# Power_supply.net
KiCad netlist of a schematic drawn in Altium Designer
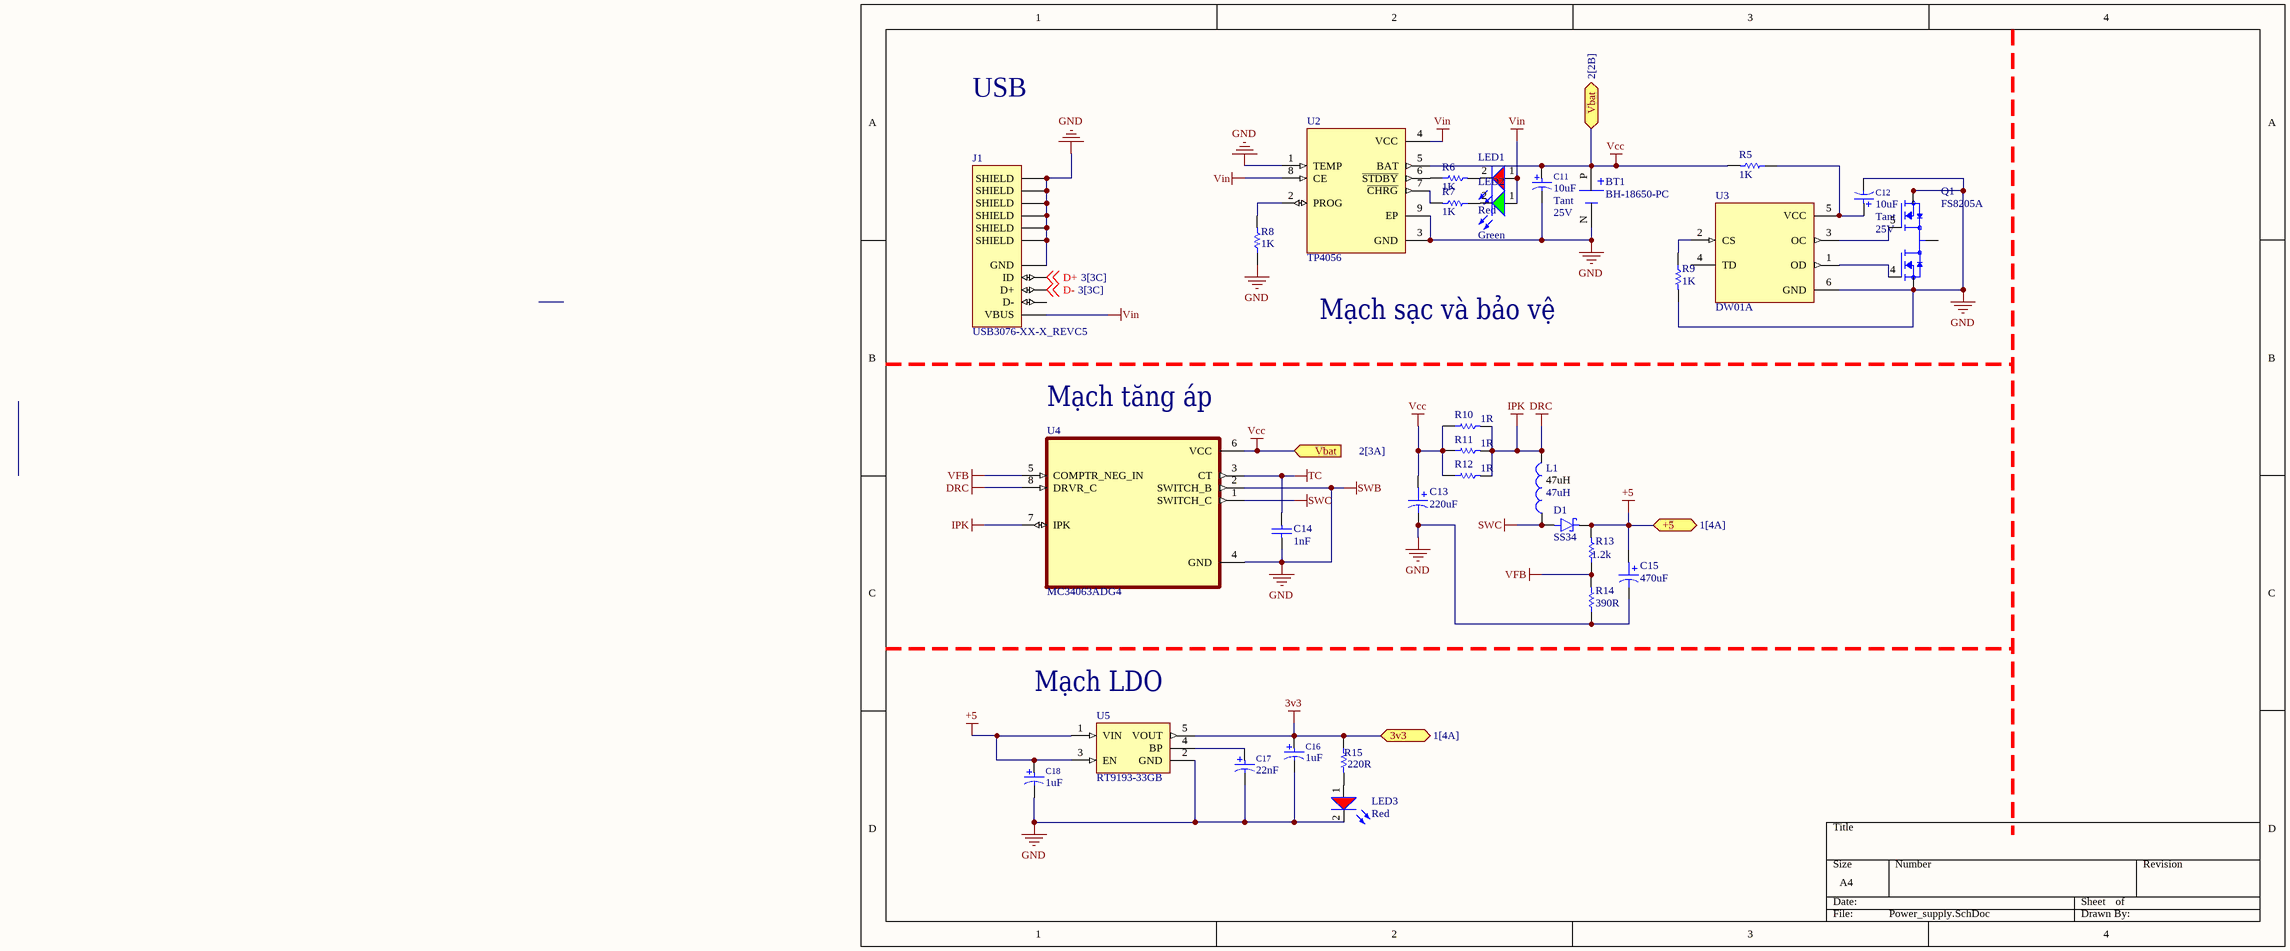
[diagram p0: Power_supply.SchDoc]

(export (version "E")
  (design (tool "Eeschema 10.0.6"))
  (components
    (comp (ref "BT1")
      (value "BH-18650-PC")
      (footprint "BAT_BH-18650-PC")
      (description "Battery Holder _Open_ 18650 1 Cell PC Pin")
      (fields (field (name "MF") "MPD _Memory"))
      (libsource (lib "BH-18650-PC") (part "BH-18650-PC"))
    )
    (comp (ref "C11")
      (value "10uF")
      (footprint "C2012-0805")
      (description "Polarized Capacitor")
      (fields
        (field (name "MANUFACTURER") "FARNELL")
        (field (name "CAPACITOR TYPE") "Tant")
        (field (name "VOLT") "25V")
        (field (name "PUBLISHER") "Hoang Nguyen")
      )
      (libsource (lib "PhongLib") (part "Cap_Pol"))
    )
    (comp (ref "C12")
      (value "10uF")
      (footprint "C2012-0805")
      (description "Polarized Capacitor")
      (fields
        (field (name "MANUFACTURER") "FARNELL")
        (field (name "CAPACITOR TYPE") "Tant")
        (field (name "VOLT") "25V")
        (field (name "PUBLISHER") "Hoang Nguyen")
      )
      (libsource (lib "PhongLib") (part "Cap_Pol"))
    )
    (comp (ref "C13")
      (value "220uF")
      (footprint "RADIAL B")
      (description "Polarized Capacitor")
      (fields (field (name "Comment") "Cap Pol") (field (name "PUBLISHER") "Altium Limited"))
      (libsource (lib "Kiet") (part "Cap Pol"))
    )
    (comp (ref "C14")
      (value "1nF")
      (footprint "C-NP-0805")
      (description "Non-polarized Capacitor")
      (fields (field (name "Comment") "Cap Non-pol") (field (name "PUBLISHER") "Altium Limited"))
      (libsource (lib "Kiet") (part "Cap Non-pol"))
    )
    (comp (ref "C15")
      (value "470uF")
      (footprint "RADIAL C")
      (description "Polarized Capacitor")
      (fields (field (name "Comment") "Cap Pol") (field (name "PUBLISHER") "Altium Limited"))
      (libsource (lib "Kiet") (part "Cap Pol"))
    )
    (comp (ref "C16")
      (value "1uF")
      (footprint "C2012-0805")
      (description "Polarized Capacitor")
      (fields (field (name "MANUFACTURER") "FARNELL") (field (name "PUBLISHER") "Hoang Nguyen"))
      (libsource (lib "PhongLib") (part "Cap_Pol"))
    )
    (comp (ref "C17")
      (value "22nF")
      (footprint "C2012-0805")
      (description "Polarized Capacitor")
      (fields (field (name "MANUFACTURER") "FARNELL") (field (name "PUBLISHER") "Hoang Nguyen"))
      (libsource (lib "PhongLib") (part "Cap_Pol"))
    )
    (comp (ref "C18")
      (value "1uF")
      (footprint "C2012-0805")
      (description "Polarized Capacitor")
      (fields (field (name "MANUFACTURER") "FARNELL") (field (name "PUBLISHER") "Hoang Nguyen"))
      (libsource (lib "PhongLib") (part "Cap_Pol"))
    )
    (comp (ref "D1")
      (value "SS34")
      (footprint "DIOM7959X265N")
      (description "Diode Schottky 40 V 3A Surface Mount SMC (DO-214AB)")
      (fields (field (name "MF") "onsemi"))
      (libsource (lib "SS34") (part "SS34"))
    )
    (comp (ref "J1")
      (value "USB3076-XX-X_REVC5")
      (footprint "GCT_USB3076-XX-X_REVC5")
      (fields (field (name "MP") "USB3076-30-A") (field (name "MF") "Global Connector Technology"))
      (libsource (lib "USB3076-XX-X_REVC5") (part "USB3076-XX-X_REVC5"))
    )
    (comp (ref "L1")
      (value "47uH")
      (footprint "IMPE8-RS2")
      (description "Cuon Cam L")
      (fields (field (name "ALTIUM_VALUE") "47uH") (field (name "PUBLISHER") "Altium Limited"))
      (libsource (lib "Kiet") (part "Inductor_1"))
    )
    (comp (ref "LED1")
      (value "Red")
      (footprint "Led 0805R")
      (description "LED Red 2mA 1.8V 0805")
      (fields (field (name "Comment") "LED-0805RVC"))
      (libsource (lib "thuvienhoang") (part "LED-0805RVC"))
    )
    (comp (ref "LED2")
      (value "Green")
      (footprint "Led 0805G")
      (description "LED Green 2mA 3V 0805")
      (fields (field (name "Comment") "LED-0805GVC"))
      (libsource (lib "thuvienhoang") (part "LED-0805GVC"))
    )
    (comp (ref "LED3")
      (value "Red")
      (footprint "Led 0805R")
      (description "LED Red 2mA 1.8V 0805")
      (fields (field (name "Comment") "LED-0805RVC"))
      (libsource (lib "thuvienhoang") (part "LED-0805RVC"))
    )
    (comp (ref "Q1")
      (value "FS8205A")
      (footprint "SOP65P640X120-8N")
      (fields (field (name "MF") "Fortune Semiconductor"))
      (libsource (lib "FS8205A") (part "FS8205A"))
    )
    (comp (ref "R5")
      (value "1K")
      (footprint "RES-SM-0805")
      (description "Resistor")
      (fields (field (name "Comment") "RESISTOR SMD"))
      (libsource (lib "thuvienhoang") (part "RESISTOR SMD"))
    )
    (comp (ref "R6")
      (value "1K")
      (footprint "RES-SM-0805")
      (description "Resistor")
      (fields (field (name "Comment") "RESISTOR SMD"))
      (libsource (lib "thuvienhoang") (part "RESISTOR SMD"))
    )
    (comp (ref "R7")
      (value "1K")
      (footprint "RES-SM-0805")
      (description "Resistor")
      (fields (field (name "Comment") "RESISTOR SMD"))
      (libsource (lib "thuvienhoang") (part "RESISTOR SMD"))
    )
    (comp (ref "R8")
      (value "1K")
      (footprint "RES-SM-0805")
      (description "Resistor")
      (fields (field (name "Comment") "RESISTOR SMD"))
      (libsource (lib "thuvienhoang") (part "RESISTOR SMD"))
    )
    (comp (ref "R9")
      (value "1K")
      (footprint "RES-SM-0805")
      (description "Resistor")
      (fields (field (name "Comment") "RESISTOR SMD"))
      (libsource (lib "thuvienhoang") (part "RESISTOR SMD"))
    )
    (comp (ref "R10")
      (value "1R")
      (footprint "R-0805")
      (description "Resistor")
      (fields (field (name "Comment") "RESISTOR") (field (name "PUBLISHER") "Altium Limited"))
      (libsource (lib "Kiet") (part "RESISTOR"))
    )
    (comp (ref "R11")
      (value "1R")
      (footprint "R-0805")
      (description "Resistor")
      (fields (field (name "Comment") "RESISTOR") (field (name "PUBLISHER") "Altium Limited"))
      (libsource (lib "Kiet") (part "RESISTOR"))
    )
    (comp (ref "R12")
      (value "1R")
      (footprint "R-0805")
      (description "Resistor")
      (fields (field (name "Comment") "RESISTOR") (field (name "PUBLISHER") "Altium Limited"))
      (libsource (lib "Kiet") (part "RESISTOR"))
    )
    (comp (ref "R13")
      (value "1.2k")
      (footprint "R-0805")
      (description "Resistor")
      (fields (field (name "Comment") "RESISTOR") (field (name "PUBLISHER") "Altium Limited"))
      (libsource (lib "Kiet") (part "RESISTOR"))
    )
    (comp (ref "R14")
      (value "390R")
      (footprint "R-0805")
      (description "Resistor")
      (fields (field (name "Comment") "RESISTOR") (field (name "PUBLISHER") "Altium Limited"))
      (libsource (lib "Kiet") (part "RESISTOR"))
    )
    (comp (ref "R15")
      (value "220R")
      (footprint "RES-SM-0805")
      (description "Resistor")
      (fields (field (name "Comment") "RESISTOR SMD"))
      (libsource (lib "thuvienhoang") (part "RESISTOR SMD"))
    )
    (comp (ref "U2")
      (value "TP4056")
      (footprint "SOP127P600X175-9N")
      (description "Complete single cell Li-Ion battery with a constant current / constant voltage linear charger")
      (fields (field (name "MF") "NanJing Top Power ASIC Corp."))
      (libsource (lib "TP4056") (part "TP4056"))
    )
    (comp (ref "U3")
      (value "DW01A")
      (footprint "SOT95P280X145-6N")
      (description "One Cell Lithium-ion/Polymer Battery Protection IC")
      (fields (field (name "MF") "Fortune Semiconductor"))
      (libsource (lib "DW01A") (part "DW01A"))
    )
    (comp (ref "U4")
      (value "MC34063ADG4")
      (footprint "SOIC127P599X175-8N")
      (libsource (lib "MC34063ADG4") (part "MC34063ADG4"))
    )
    (comp (ref "U5")
      (value "RT9193-33GB")
      (footprint "SOT94P279X129-5N")
      (description "Linear Voltage Regulator IC Positive Fixed 1 Output 300mA TSOT-23-5")
      (fields (field (name "MF") "Richtek USA") (field (name "DIGI-KEY_PART_NUMBER") "1028-1014-2-ND"))
      (libsource (lib "RT9193-33GB") (part "RT9193-33GB"))
    )
  )
  (nets
    (net (code "1") (name "+5") (class "Default")
      (node (ref "C15") (pin "1") (pinfunction "1_1") (pintype "passive"))
      (node (ref "C18") (pin "1") (pinfunction "1_1") (pintype "passive"))
      (node (ref "D1") (pin "C") (pinfunction "K_C") (pintype "passive"))
      (node (ref "R13") (pin "2") (pinfunction "2_2") (pintype "passive"))
      (node (ref "U5") (pin "1") (pinfunction "VIN_1") (pintype "input"))
      (node (ref "U5") (pin "3") (pinfunction "EN_3") (pintype "input"))
    )
    (net (code "2") (name "3v3") (class "Default")
      (node (ref "C16") (pin "1") (pinfunction "1_1") (pintype "passive"))
      (node (ref "R15") (pin "1") (pinfunction "1_1") (pintype "passive"))
      (node (ref "U5") (pin "5") (pinfunction "VOUT_5") (pintype "output"))
    )
    (net (code "3") (name "D+") (class "Default")
      (node (ref "J1") (pin "4") (pinfunction "ID_4") (pintype "bidirectional"))
    )
    (net (code "4") (name "D-") (class "Default")
      (node (ref "J1") (pin "3") (pinfunction "D+_3") (pintype "bidirectional"))
    )
    (net (code "5") (name "DRC") (class "Default")
      (node (ref "L1") (pin "2") (pinfunction "2_2") (pintype "passive"))
      (node (ref "R10") (pin "2") (pinfunction "2_2") (pintype "passive"))
      (node (ref "R11") (pin "2") (pinfunction "2_2") (pintype "passive"))
      (node (ref "R12") (pin "2") (pinfunction "2_2") (pintype "passive"))
      (node (ref "U4") (pin "7") (pinfunction "IPK_7") (pintype "bidirectional"))
      (node (ref "U4") (pin "8") (pinfunction "DRVR_C_8") (pintype "input"))
    )
    (net (code "6") (name "GND") (class "Default")
      (node (ref "BT1") (pin "N") (pinfunction "NEG_N") (pintype "passive"))
      (node (ref "C11") (pin "2") (pinfunction "2_2") (pintype "passive"))
      (node (ref "C12") (pin "2") (pinfunction "2_2") (pintype "passive"))
      (node (ref "C13") (pin "2") (pinfunction "2_2") (pintype "passive"))
      (node (ref "C14") (pin "1") (pinfunction "1_1") (pintype "passive"))
      (node (ref "C15") (pin "2") (pinfunction "2_2") (pintype "passive"))
      (node (ref "C16") (pin "2") (pinfunction "2_2") (pintype "passive"))
      (node (ref "C17") (pin "2") (pinfunction "2_2") (pintype "passive"))
      (node (ref "C18") (pin "2") (pinfunction "2_2") (pintype "passive"))
      (node (ref "J1") (pin "10") (pinfunction "SHIELD_10") (pintype "power_in"))
      (node (ref "J1") (pin "11") (pinfunction "SHIELD_11") (pintype "power_in"))
      (node (ref "J1") (pin "5") (pinfunction "GND_5") (pintype "power_in"))
      (node (ref "J1") (pin "6") (pinfunction "SHIELD_6") (pintype "power_in"))
      (node (ref "J1") (pin "7") (pinfunction "SHIELD_7") (pintype "power_in"))
      (node (ref "J1") (pin "8") (pinfunction "SHIELD_8") (pintype "power_in"))
      (node (ref "J1") (pin "9") (pinfunction "SHIELD_9") (pintype "power_in"))
      (node (ref "LED3") (pin "2") (pinfunction "K_2") (pintype "passive"))
      (node (ref "Q1") (pin "2") (pinfunction "S1_2") (pintype "passive"))
      (node (ref "Q1") (pin "3") (pinfunction "S1_3") (pintype "passive"))
      (node (ref "Q1") (pin "6") (pinfunction "S2_6") (pintype "passive"))
      (node (ref "Q1") (pin "7") (pinfunction "S2_7") (pintype "passive"))
      (node (ref "R14") (pin "1") (pinfunction "1_1") (pintype "passive"))
      (node (ref "R8") (pin "1") (pinfunction "1_1") (pintype "passive"))
      (node (ref "R9") (pin "2") (pinfunction "2_2") (pintype "passive"))
      (node (ref "U2") (pin "1") (pinfunction "TEMP_1") (pintype "input"))
      (node (ref "U2") (pin "3") (pinfunction "GND_3") (pintype "power_in"))
      (node (ref "U2") (pin "9") (pinfunction "EP_9") (pintype "passive"))
      (node (ref "U3") (pin "6") (pinfunction "GND_6") (pintype "power_in"))
      (node (ref "U4") (pin "2") (pinfunction "SWITCH_B_2") (pintype "output"))
      (node (ref "U4") (pin "4") (pinfunction "GND_4") (pintype "power_in"))
      (node (ref "U5") (pin "2") (pinfunction "GND_2") (pintype "power_in"))
    )
    (net (code "7") (name "Net-(LED1-K)") (class "Default")
      (node (ref "LED1") (pin "2") (pinfunction "K_2") (pintype "passive"))
      (node (ref "R6") (pin "2") (pinfunction "2_2") (pintype "passive"))
    )
    (net (code "8") (name "Net-(LED2-K)") (class "Default")
      (node (ref "LED2") (pin "2") (pinfunction "K_2") (pintype "passive"))
      (node (ref "R7") (pin "1") (pinfunction "1_1") (pintype "passive"))
    )
    (net (code "9") (name "Net-(LED3-A)") (class "Default")
      (node (ref "LED3") (pin "1") (pinfunction "A_1") (pintype "passive"))
      (node (ref "R15") (pin "2") (pinfunction "2_2") (pintype "passive"))
    )
    (net (code "10") (name "Net-(Q1-D12-Pad1)") (class "Default")
      (node (ref "Q1") (pin "1") (pinfunction "D12_1") (pintype "passive"))
      (node (ref "Q1") (pin "8") (pinfunction "D12_8") (pintype "passive"))
    )
    (net (code "11") (name "Net-(Q1-G1)") (class "Default")
      (node (ref "Q1") (pin "4") (pinfunction "G1_4") (pintype "passive"))
      (node (ref "U3") (pin "1") (pinfunction "OD_1") (pintype "output"))
    )
    (net (code "12") (name "Net-(Q1-G2)") (class "Default")
      (node (ref "Q1") (pin "5") (pinfunction "G2_5") (pintype "passive"))
      (node (ref "U3") (pin "3") (pinfunction "OC_3") (pintype "output"))
    )
    (net (code "13") (name "Net-(U2-PROG)") (class "Default")
      (node (ref "R8") (pin "2") (pinfunction "2_2") (pintype "passive"))
      (node (ref "U2") (pin "2") (pinfunction "PROG_2") (pintype "bidirectional"))
    )
    (net (code "14") (name "Net-(U2-~{CHRG})") (class "Default")
      (node (ref "R7") (pin "2") (pinfunction "2_2") (pintype "passive"))
      (node (ref "U2") (pin "7") (pinfunction "~{CHRG}_7") (pintype "output"))
    )
    (net (code "15") (name "Net-(U2-~{STDBY})") (class "Default")
      (node (ref "R6") (pin "1") (pinfunction "1_1") (pintype "passive"))
      (node (ref "U2") (pin "6") (pinfunction "~{STDBY}_6") (pintype "output"))
    )
    (net (code "16") (name "Net-(U3-CS)") (class "Default")
      (node (ref "R9") (pin "1") (pinfunction "1_1") (pintype "passive"))
      (node (ref "U3") (pin "2") (pinfunction "CS_2") (pintype "input"))
    )
    (net (code "17") (name "Net-(U3-VCC)") (class "Default")
      (node (ref "C12") (pin "1") (pinfunction "1_1") (pintype "passive"))
      (node (ref "R5") (pin "1") (pinfunction "1_1") (pintype "passive"))
      (node (ref "U3") (pin "5") (pinfunction "VCC_5") (pintype "power_in"))
    )
    (net (code "18") (name "Net-(U5-BP)") (class "Default")
      (node (ref "C17") (pin "1") (pinfunction "1_1") (pintype "passive"))
      (node (ref "U5") (pin "4") (pinfunction "BP_4") (pintype "passive"))
    )
    (net (code "19") (name "SWC") (class "Default")
      (node (ref "D1") (pin "A") (pinfunction "A_A") (pintype "passive"))
      (node (ref "L1") (pin "1") (pinfunction "1_1") (pintype "passive"))
      (node (ref "U4") (pin "1") (pinfunction "SWITCH_C_1") (pintype "output"))
    )
    (net (code "20") (name "TC") (class "Default")
      (node (ref "C14") (pin "2") (pinfunction "2_2") (pintype "passive"))
      (node (ref "U4") (pin "3") (pinfunction "CT_3") (pintype "output"))
    )
    (net (code "21") (name "VFB") (class "Default")
      (node (ref "R13") (pin "1") (pinfunction "1_1") (pintype "passive"))
      (node (ref "R14") (pin "2") (pinfunction "2_2") (pintype "passive"))
      (node (ref "U4") (pin "5") (pinfunction "COMPTR_NEG_IN_5") (pintype "input"))
    )
    (net (code "22") (name "Vcc") (class "Default")
      (node (ref "BT1") (pin "P") (pinfunction "POS_P") (pintype "passive"))
      (node (ref "C11") (pin "1") (pinfunction "1_1") (pintype "passive"))
      (node (ref "C13") (pin "1") (pinfunction "1_1") (pintype "passive"))
      (node (ref "R10") (pin "1") (pinfunction "1_1") (pintype "passive"))
      (node (ref "R11") (pin "1") (pinfunction "1_1") (pintype "passive"))
      (node (ref "R12") (pin "1") (pinfunction "1_1") (pintype "passive"))
      (node (ref "R5") (pin "2") (pinfunction "2_2") (pintype "passive"))
      (node (ref "U2") (pin "5") (pinfunction "BAT_5") (pintype "output"))
      (node (ref "U4") (pin "6") (pinfunction "VCC_6") (pintype "power_in"))
    )
    (net (code "23") (name "Vin") (class "Default")
      (node (ref "J1") (pin "1") (pinfunction "VBUS_1") (pintype "power_in"))
      (node (ref "LED1") (pin "1") (pinfunction "A_1") (pintype "passive"))
      (node (ref "LED2") (pin "1") (pinfunction "A_1") (pintype "passive"))
      (node (ref "U2") (pin "4") (pinfunction "VCC_4") (pintype "power_in"))
      (node (ref "U2") (pin "8") (pinfunction "CE_8") (pintype "input"))
    )
    (net (code "24") (name "unconnected-(J1-D--Pad2)") (class "Default")
      (node (ref "J1") (pin "2") (pinfunction "D-_2") (pintype "bidirectional"))
    )
    (net (code "25") (name "unconnected-(U3-TD-Pad4)") (class "Default")
      (node (ref "U3") (pin "4") (pinfunction "TD_4") (pintype "passive"))
    )
  )
)
